# 07_ESP-12F_Circuit.net
KiCad netlist of a schematic drawn in Altium Designer
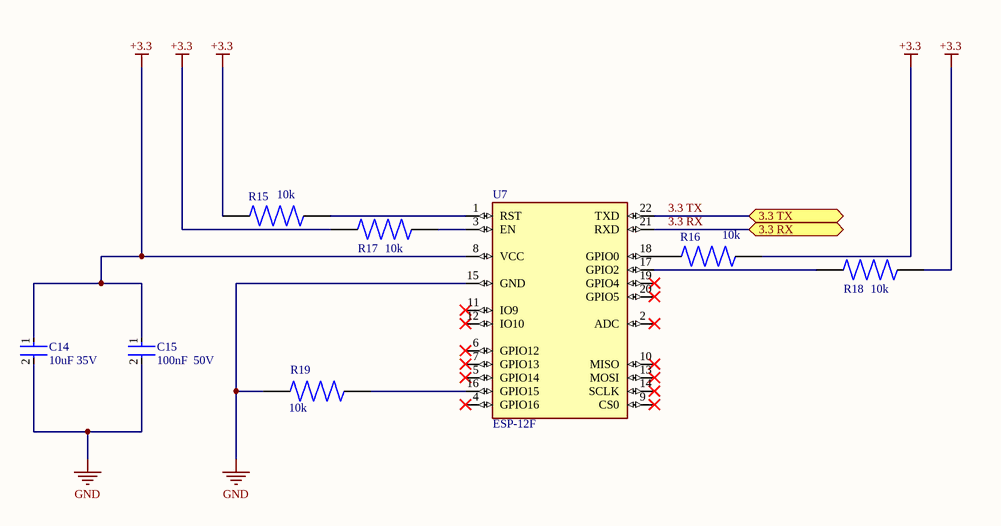
[diagram p0: 07_ESP-12F_Circuit.SchDoc]

(export (version "E")
  (design (tool "Eeschema 10.0.6"))
  (components
    (comp (ref "C14")
      (value "10uF 35V")
      (footprint "FP-GRM21B-0_2-e0_2_0_7-IPC_B")
      (description "Chip Multilayer Ceramic Capacitors for General Purpose, 0805, 10uF, X5R, 15%, 20%, 35V")
      (fields (field (name "TOLERANCE") "20%"))
      (libsource (lib "Altium Content Vault") (part "b4654b650e69147ec39a6b967a45e02"))
    )
    (comp (ref "C15")
      (value "100nF  50V")
      (footprint "FP-0805-L_2_01_0_2-W_1_25-IPC_C")
      (description "General Purpose Ceramic Capacitor, 0805, 100nF, 10%, X7R, 0.15, 50V")
      (fields (field (name "TOLERANCE") "10%") (field (name "VOLTAGE") "50V"))
      (libsource (lib "Altium Content Vault") (part "02cd4be3c70576c341d710602a673aa"))
    )
    (comp (ref "R15")
      (value "10k")
      (footprint "RESC3115X65N")
      (description "10K Ohm 1/4W Thick Film Resistor 1206 Chip - Surface Mount")
      (fields (field (name "MF") "Uni-Royal") (field (name "MP") "1206W4F1002T5E"))
      (libsource (lib "1206W4F1002T5E") (part "1206W4F1002T5E"))
    )
    (comp (ref "R16")
      (value "10k")
      (footprint "RESC3115X65N")
      (description "10K Ohm 1/4W Thick Film Resistor 1206 Chip - Surface Mount")
      (fields (field (name "MF") "Uni-Royal") (field (name "MP") "1206W4F1002T5E"))
      (libsource (lib "1206W4F1002T5E") (part "1206W4F1002T5E"))
    )
    (comp (ref "R17")
      (value "10k")
      (footprint "RESC3115X65N")
      (description "10K Ohm 1/4W Thick Film Resistor 1206 Chip - Surface Mount")
      (fields (field (name "MF") "Uni-Royal") (field (name "MP") "1206W4F1002T5E"))
      (libsource (lib "1206W4F1002T5E") (part "1206W4F1002T5E"))
    )
    (comp (ref "R18")
      (value "10k")
      (footprint "RESC3115X65N")
      (description "10K Ohm 1/4W Thick Film Resistor 1206 Chip - Surface Mount")
      (fields (field (name "MF") "Uni-Royal") (field (name "MP") "1206W4F1002T5E"))
      (libsource (lib "1206W4F1002T5E") (part "1206W4F1002T5E"))
    )
    (comp (ref "R19")
      (value "10k")
      (footprint "RESC3115X65N")
      (description "10K Ohm 1/4W Thick Film Resistor 1206 Chip - Surface Mount")
      (fields (field (name "MF") "Uni-Royal") (field (name "MP") "1206W4F1002T5E"))
      (libsource (lib "1206W4F1002T5E") (part "1206W4F1002T5E"))
    )
    (comp (ref "U7")
      (value "ESP-12F")
      (footprint "ESP-12F")
      (description "WiFi Module")
      (fields (field (name "MF") "AI-Thinker"))
      (libsource (lib "ESP-12F") (part "ESP-12F"))
    )
  )
  (nets
    (net (code "1") (name "+3.3") (class "Default")
      (node (ref "C14") (pin "1") (pinfunction "1_1") (pintype "passive"))
      (node (ref "C15") (pin "1") (pinfunction "1_1") (pintype "passive"))
      (node (ref "R15") (pin "1") (pinfunction "1_1") (pintype "passive"))
      (node (ref "R16") (pin "2") (pinfunction "2_2") (pintype "passive"))
      (node (ref "R17") (pin "1") (pinfunction "1_1") (pintype "passive"))
      (node (ref "R18") (pin "2") (pinfunction "2_2") (pintype "passive"))
      (node (ref "U7") (pin "8") (pinfunction "VCC_8") (pintype "bidirectional"))
    )
    (net (code "2") (name "/3.3 RX") (class "Default")
      (node (ref "U7") (pin "21") (pinfunction "RXD_21") (pintype "bidirectional"))
    )
    (net (code "3") (name "/3.3 TX") (class "Default")
      (node (ref "U7") (pin "22") (pinfunction "TXD_22") (pintype "bidirectional"))
    )
    (net (code "4") (name "GND") (class "Default")
      (node (ref "C14") (pin "2") (pinfunction "2_2") (pintype "passive"))
      (node (ref "C15") (pin "2") (pinfunction "2_2") (pintype "passive"))
      (node (ref "R19") (pin "1") (pinfunction "1_1") (pintype "passive"))
      (node (ref "U7") (pin "15") (pinfunction "GND_15") (pintype "bidirectional"))
    )
    (net (code "5") (name "Net-(U7-EN)") (class "Default")
      (node (ref "R17") (pin "2") (pinfunction "2_2") (pintype "passive"))
      (node (ref "U7") (pin "3") (pinfunction "EN_3") (pintype "bidirectional"))
    )
    (net (code "6") (name "Net-(U7-GPIO0)") (class "Default")
      (node (ref "R16") (pin "1") (pinfunction "1_1") (pintype "passive"))
      (node (ref "U7") (pin "18") (pinfunction "GPIO0_18") (pintype "bidirectional"))
    )
    (net (code "7") (name "Net-(U7-GPIO2)") (class "Default")
      (node (ref "R18") (pin "1") (pinfunction "1_1") (pintype "passive"))
      (node (ref "U7") (pin "17") (pinfunction "GPIO2_17") (pintype "bidirectional"))
    )
    (net (code "8") (name "Net-(U7-GPIO15)") (class "Default")
      (node (ref "R19") (pin "2") (pinfunction "2_2") (pintype "passive"))
      (node (ref "U7") (pin "16") (pinfunction "GPIO15_16") (pintype "bidirectional"))
    )
    (net (code "9") (name "Net-(U7-RST)") (class "Default")
      (node (ref "R15") (pin "2") (pinfunction "2_2") (pintype "passive"))
      (node (ref "U7") (pin "1") (pinfunction "RST_1") (pintype "bidirectional"))
    )
    (net (code "10") (name "unconnected-(U7-ADC-Pad2)") (class "Default")
      (node (ref "U7") (pin "2") (pinfunction "ADC_2") (pintype "bidirectional+no_connect"))
    )
    (net (code "11") (name "unconnected-(U7-CS0-Pad9)") (class "Default")
      (node (ref "U7") (pin "9") (pinfunction "CS0_9") (pintype "bidirectional+no_connect"))
    )
    (net (code "12") (name "unconnected-(U7-GPIO4-Pad19)") (class "Default")
      (node (ref "U7") (pin "19") (pinfunction "GPIO4_19") (pintype "bidirectional+no_connect"))
    )
    (net (code "13") (name "unconnected-(U7-GPIO5-Pad20)") (class "Default")
      (node (ref "U7") (pin "20") (pinfunction "GPIO5_20") (pintype "bidirectional+no_connect"))
    )
    (net (code "14") (name "unconnected-(U7-GPIO12-Pad6)") (class "Default")
      (node (ref "U7") (pin "6") (pinfunction "GPIO12_6") (pintype "bidirectional+no_connect"))
    )
    (net (code "15") (name "unconnected-(U7-GPIO13-Pad7)") (class "Default")
      (node (ref "U7") (pin "7") (pinfunction "GPIO13_7") (pintype "bidirectional+no_connect"))
    )
    (net (code "16") (name "unconnected-(U7-GPIO14-Pad5)") (class "Default")
      (node (ref "U7") (pin "5") (pinfunction "GPIO14_5") (pintype "bidirectional+no_connect"))
    )
    (net (code "17") (name "unconnected-(U7-GPIO16-Pad4)") (class "Default")
      (node (ref "U7") (pin "4") (pinfunction "GPIO16_4") (pintype "bidirectional+no_connect"))
    )
    (net (code "18") (name "unconnected-(U7-IO9-Pad11)") (class "Default")
      (node (ref "U7") (pin "11") (pinfunction "IO9_11") (pintype "bidirectional+no_connect"))
    )
    (net (code "19") (name "unconnected-(U7-IO10-Pad12)") (class "Default")
      (node (ref "U7") (pin "12") (pinfunction "IO10_12") (pintype "bidirectional+no_connect"))
    )
    (net (code "20") (name "unconnected-(U7-MISO-Pad10)") (class "Default")
      (node (ref "U7") (pin "10") (pinfunction "MISO_10") (pintype "bidirectional+no_connect"))
    )
    (net (code "21") (name "unconnected-(U7-MOSI-Pad13)") (class "Default")
      (node (ref "U7") (pin "13") (pinfunction "MOSI_13") (pintype "bidirectional+no_connect"))
    )
    (net (code "22") (name "unconnected-(U7-SCLK-Pad14)") (class "Default")
      (node (ref "U7") (pin "14") (pinfunction "SCLK_14") (pintype "bidirectional+no_connect"))
    )
  )
)
